# Schematic.net
KiCad netlist of a schematic drawn in Altium Designer
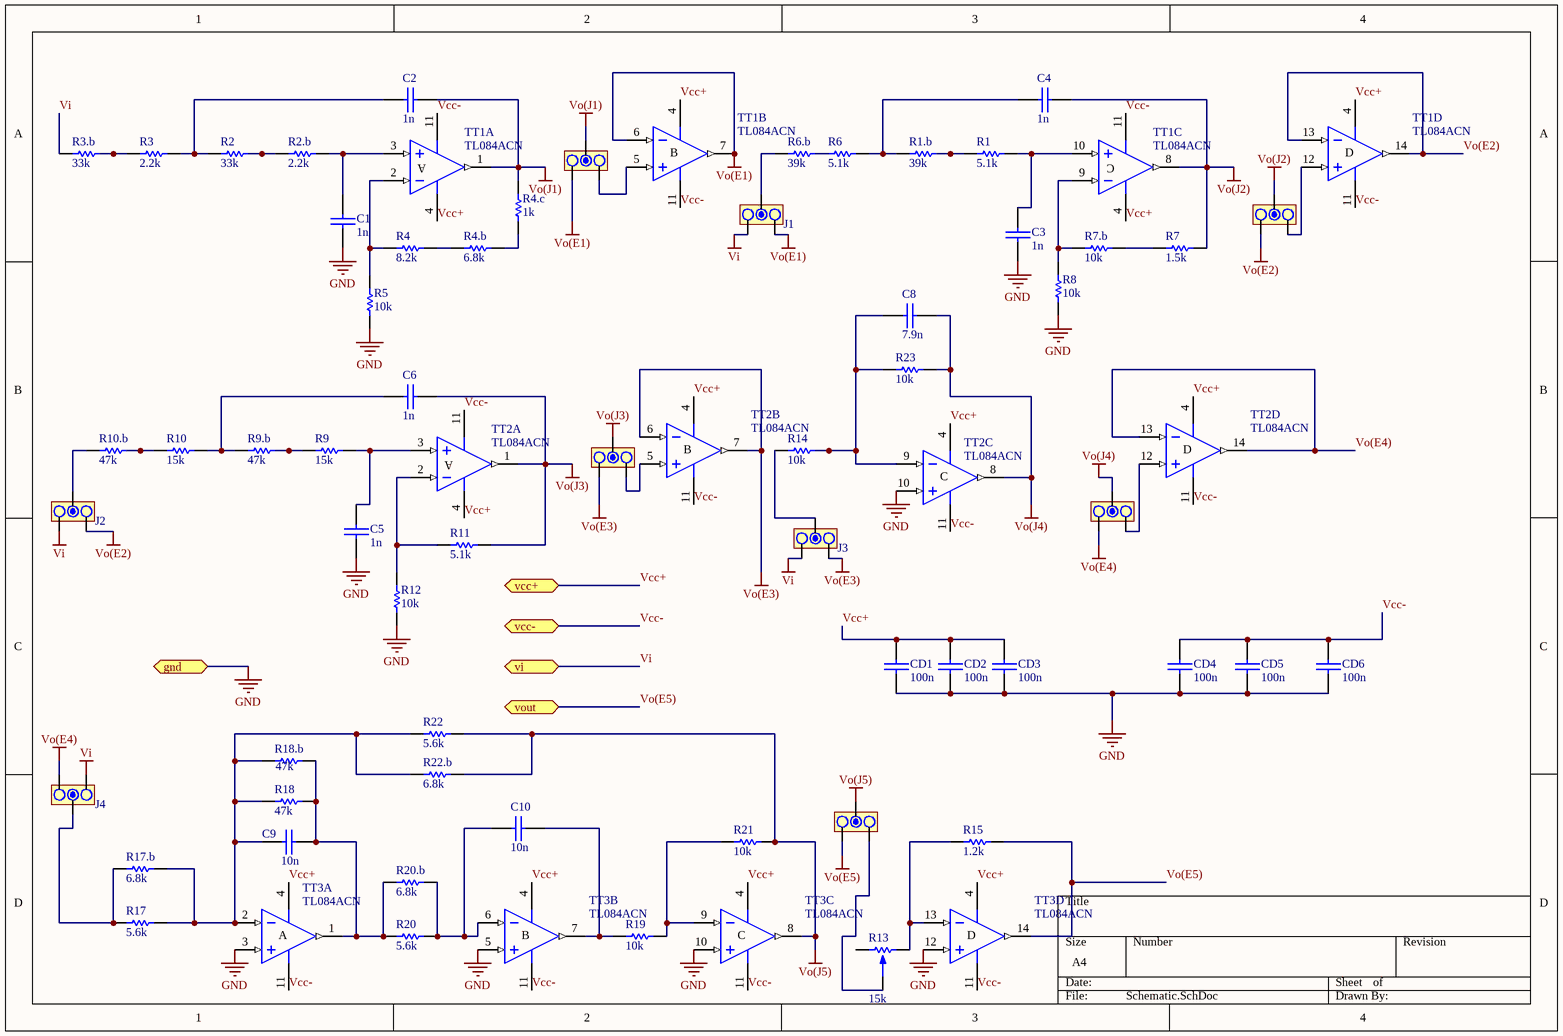
[diagram p0: Schematic.SchDoc]

(export (version "E")
  (design (tool "Eeschema 10.0.6"))
  (components
    (comp (ref "C1") (value "1n") (footprint "CAP200") (libsource (lib "LIBEBAL") (part "CAP")))
    (comp (ref "C2") (value "1n") (footprint "CAP200") (libsource (lib "LIBEBAL") (part "CAP")))
    (comp (ref "C3") (value "1n") (footprint "CAP200") (libsource (lib "LIBEBAL") (part "CAP")))
    (comp (ref "C4") (value "1n") (footprint "CAP200") (libsource (lib "LIBEBAL") (part "CAP")))
    (comp (ref "C5") (value "1n") (footprint "CAP200") (libsource (lib "LIBEBAL") (part "CAP")))
    (comp (ref "C6") (value "1n") (footprint "CAP200") (libsource (lib "LIBEBAL") (part "CAP")))
    (comp (ref "C8") (value "7.9n") (footprint "CAP200") (libsource (lib "LIBEBAL") (part "CAP")))
    (comp (ref "C9") (value "10n") (footprint "CAP200") (libsource (lib "LIBEBAL") (part "CAP")))
    (comp (ref "C10") (value "10n") (footprint "CAP200") (libsource (lib "LIBEBAL") (part "CAP")))
    (comp (ref "CD1") (value "100n") (footprint "CAP200") (libsource (lib "LIBEBAL") (part "CAP")))
    (comp (ref "CD2") (value "100n") (footprint "CAP200") (libsource (lib "LIBEBAL") (part "CAP")))
    (comp (ref "CD3") (value "100n") (footprint "CAP200") (libsource (lib "LIBEBAL") (part "CAP")))
    (comp (ref "CD4") (value "100n") (footprint "CAP200") (libsource (lib "LIBEBAL") (part "CAP")))
    (comp (ref "CD5") (value "100n") (footprint "CAP200") (libsource (lib "LIBEBAL") (part "CAP")))
    (comp (ref "CD6") (value "100n") (footprint "CAP200") (libsource (lib "LIBEBAL") (part "CAP")))
    (comp (ref "J1") (value "JUMPER") (footprint "JUMPER3") (libsource (lib "LIBEBAL") (part "JUMPER3")))
    (comp (ref "J2") (value "JUMPER") (footprint "JUMPER3") (libsource (lib "LIBEBAL") (part "JUMPER3")))
    (comp (ref "J3") (value "JUMPER") (footprint "JUMPER3") (libsource (lib "LIBEBAL") (part "JUMPER3")))
    (comp (ref "J4") (value "JUMPER") (footprint "JUMPER3") (libsource (lib "") (part "JUMPER3_1")))
    (comp (ref "Jumper1") (value "JUMPER") (footprint "JUMPER3") (libsource (lib "LIBEBAL") (part "JUMPER3")))
    (comp (ref "Jumper2") (value "JUMPER") (footprint "JUMPER3") (libsource (lib "LIBEBAL") (part "JUMPER3")))
    (comp (ref "Jumper3") (value "JUMPER") (footprint "JUMPER3") (libsource (lib "LIBEBAL") (part "JUMPER3")))
    (comp (ref "Jumper4") (value "JUMPER") (footprint "JUMPER3") (libsource (lib "LIBEBAL") (part "JUMPER3")))
    (comp (ref "Jumper5") (value "JUMPER") (footprint "JUMPER3") (libsource (lib "LIBEBAL") (part "JUMPER3")))
    (comp (ref "R1") (value "5.1k") (footprint "RES400") (libsource (lib "LIBEBAL") (part "RES")))
    (comp (ref "R1.b") (value "39k") (footprint "RES400") (libsource (lib "LIBEBAL") (part "RES")))
    (comp (ref "R2") (value "33k") (footprint "RES400") (libsource (lib "LIBEBAL") (part "RES")))
    (comp (ref "R2.b") (value "2.2k") (footprint "RES400") (libsource (lib "LIBEBAL") (part "RES")))
    (comp (ref "R3") (value "2.2k") (footprint "RES400") (libsource (lib "LIBEBAL") (part "RES")))
    (comp (ref "R3.b") (value "33k") (footprint "RES400") (libsource (lib "LIBEBAL") (part "RES")))
    (comp (ref "R4") (value "8.2k") (footprint "RES400") (libsource (lib "LIBEBAL") (part "RES")))
    (comp (ref "R4.b") (value "6.8k") (footprint "RES400") (libsource (lib "LIBEBAL") (part "RES")))
    (comp (ref "R4.c") (value "1k") (footprint "RES400") (libsource (lib "LIBEBAL") (part "RES")))
    (comp (ref "R5") (value "10k") (footprint "RES400") (libsource (lib "LIBEBAL") (part "RES")))
    (comp (ref "R6") (value "5.1k") (footprint "RES400") (libsource (lib "LIBEBAL") (part "RES")))
    (comp (ref "R6.b") (value "39k") (footprint "RES400") (libsource (lib "LIBEBAL") (part "RES")))
    (comp (ref "R7") (value "1.5k") (footprint "RES400") (libsource (lib "LIBEBAL") (part "RES")))
    (comp (ref "R7.b") (value "10k") (footprint "RES400") (libsource (lib "LIBEBAL") (part "RES")))
    (comp (ref "R8") (value "10k") (footprint "RES400") (libsource (lib "LIBEBAL") (part "RES")))
    (comp (ref "R9") (value "15k") (footprint "RES400") (libsource (lib "LIBEBAL") (part "RES")))
    (comp (ref "R9.b") (value "47k") (footprint "RES400") (libsource (lib "LIBEBAL") (part "RES")))
    (comp (ref "R10") (value "15k") (footprint "RES400") (libsource (lib "LIBEBAL") (part "RES")))
    (comp (ref "R10.b") (value "47k") (footprint "RES400") (libsource (lib "LIBEBAL") (part "RES")))
    (comp (ref "R11") (value "5.1k") (footprint "RES400") (libsource (lib "LIBEBAL") (part "RES")))
    (comp (ref "R12") (value "10k") (footprint "RES400") (libsource (lib "LIBEBAL") (part "RES")))
    (comp (ref "R13") (value "15k") (footprint "PRESET V") (libsource (lib "LIBEBAL") (part "PRESET")))
    (comp (ref "R14") (value "10k") (footprint "RES400") (libsource (lib "LIBEBAL") (part "RES")))
    (comp (ref "R15") (value "1.2k") (footprint "RES400") (libsource (lib "LIBEBAL") (part "RES")))
    (comp (ref "R17") (value "5.6k") (footprint "RES400") (libsource (lib "LIBEBAL") (part "RES")))
    (comp (ref "R17.b") (value "6.8k") (footprint "RES400") (libsource (lib "LIBEBAL") (part "RES")))
    (comp (ref "R18") (value "47k") (footprint "RES400") (libsource (lib "LIBEBAL") (part "RES")))
    (comp (ref "R18.b") (value "47k") (footprint "RES400") (libsource (lib "LIBEBAL") (part "RES")))
    (comp (ref "R19") (value "10k") (footprint "RES400") (libsource (lib "LIBEBAL") (part "RES")))
    (comp (ref "R20") (value "5.6k") (footprint "RES400") (libsource (lib "LIBEBAL") (part "RES")))
    (comp (ref "R20.b") (value "6.8k") (footprint "RES400") (libsource (lib "LIBEBAL") (part "RES")))
    (comp (ref "R21") (value "10k") (footprint "RES400") (libsource (lib "LIBEBAL") (part "RES")))
    (comp (ref "R22") (value "5.6k") (footprint "RES400") (libsource (lib "LIBEBAL") (part "RES")))
    (comp (ref "R22.b") (value "6.8k") (footprint "RES400") (libsource (lib "LIBEBAL") (part "RES")))
    (comp (ref "R23") (value "10k") (footprint "RES400") (libsource (lib "LIBEBAL") (part "RES")))
    (comp (ref "TT1")
      (value "TL084ACN")
      (footprint "DIP14")
      (description "General-Purpose J-FET Quad Operational Amplifier")
      (fields (field (name "PUBLISHER") "Altium Limited"))
      (libsource (lib "ST Operational Amplifier") (part "TL084ACN"))
    )
    (comp (ref "TT2")
      (value "TL084ACN")
      (footprint "DIP14")
      (description "General-Purpose J-FET Quad Operational Amplifier")
      (fields (field (name "PUBLISHER") "Altium Limited"))
      (libsource (lib "ST Operational Amplifier") (part "TL084ACN"))
    )
    (comp (ref "TT3")
      (value "TL084ACN")
      (footprint "DIP14")
      (description "General-Purpose J-FET Quad Operational Amplifier")
      (fields (field (name "PUBLISHER") "Altium Limited"))
      (libsource (lib "ST Operational Amplifier") (part "TL084ACN"))
    )
  )
  (nets
    (net (code "1") (name "/Vcc+") (class "Default")
      (node (ref "CD1") (pin "1") (pinfunction "1_1") (pintype "passive"))
      (node (ref "CD2") (pin "1") (pinfunction "1_1") (pintype "passive"))
      (node (ref "CD3") (pin "1") (pinfunction "1_1") (pintype "passive"))
      (node (ref "TT1") (pin "4") (pinfunction "V+_4") (pintype "power_in"))
      (node (ref "TT2") (pin "4") (pinfunction "V+_4") (pintype "power_in"))
      (node (ref "TT3") (pin "4") (pinfunction "V+_4") (pintype "power_in"))
    )
    (net (code "2") (name "/Vcc-") (class "Default")
      (node (ref "CD4") (pin "1") (pinfunction "1_1") (pintype "passive"))
      (node (ref "CD5") (pin "1") (pinfunction "1_1") (pintype "passive"))
      (node (ref "CD6") (pin "1") (pinfunction "1_1") (pintype "passive"))
      (node (ref "TT1") (pin "11") (pinfunction "V-_11") (pintype "power_in"))
      (node (ref "TT2") (pin "11") (pinfunction "V-_11") (pintype "power_in"))
      (node (ref "TT3") (pin "11") (pinfunction "V-_11") (pintype "power_in"))
    )
    (net (code "3") (name "GND") (class "Default")
      (node (ref "C1") (pin "1") (pinfunction "1_1") (pintype "passive"))
      (node (ref "C3") (pin "1") (pinfunction "1_1") (pintype "passive"))
      (node (ref "C5") (pin "1") (pinfunction "1_1") (pintype "passive"))
      (node (ref "CD1") (pin "2") (pinfunction "2_2") (pintype "passive"))
      (node (ref "CD2") (pin "2") (pinfunction "2_2") (pintype "passive"))
      (node (ref "CD3") (pin "2") (pinfunction "2_2") (pintype "passive"))
      (node (ref "CD4") (pin "2") (pinfunction "2_2") (pintype "passive"))
      (node (ref "CD5") (pin "2") (pinfunction "2_2") (pintype "passive"))
      (node (ref "CD6") (pin "2") (pinfunction "2_2") (pintype "passive"))
      (node (ref "R12") (pin "1") (pinfunction "1_1") (pintype "passive"))
      (node (ref "R5") (pin "1") (pinfunction "1_1") (pintype "passive"))
      (node (ref "R8") (pin "1") (pinfunction "1_1") (pintype "passive"))
      (node (ref "TT2") (pin "10") (pinfunction "IN+_10") (pintype "input"))
      (node (ref "TT3") (pin "10") (pinfunction "IN+_10") (pintype "input"))
      (node (ref "TT3") (pin "12") (pinfunction "IN+_12") (pintype "input"))
      (node (ref "TT3") (pin "3") (pinfunction "IN+_3") (pintype "input"))
      (node (ref "TT3") (pin "5") (pinfunction "IN+_5") (pintype "input"))
    )
    (net (code "4") (name "Net-(C2-Pad1)") (class "Default")
      (node (ref "C2") (pin "1") (pinfunction "1_1") (pintype "passive"))
      (node (ref "R2") (pin "1") (pinfunction "1_1") (pintype "passive"))
      (node (ref "R3") (pin "2") (pinfunction "2_2") (pintype "passive"))
    )
    (net (code "5") (name "Net-(C4-Pad1)") (class "Default")
      (node (ref "C4") (pin "1") (pinfunction "1_1") (pintype "passive"))
      (node (ref "R1.b") (pin "1") (pinfunction "1_1") (pintype "passive"))
      (node (ref "R6") (pin "2") (pinfunction "2_2") (pintype "passive"))
    )
    (net (code "6") (name "Net-(C6-Pad1)") (class "Default")
      (node (ref "C6") (pin "1") (pinfunction "1_1") (pintype "passive"))
      (node (ref "R10") (pin "2") (pinfunction "2_2") (pintype "passive"))
      (node (ref "R9.b") (pin "1") (pinfunction "1_1") (pintype "passive"))
    )
    (net (code "7") (name "Net-(J1-Pad2)") (class "Default")
      (node (ref "J1") (pin "2") (pinfunction "2_2") (pintype "passive"))
      (node (ref "R6.b") (pin "1") (pinfunction "1_1") (pintype "passive"))
    )
    (net (code "8") (name "Net-(J2-Pad2)") (class "Default")
      (node (ref "J2") (pin "2") (pinfunction "2_2") (pintype "passive"))
      (node (ref "R10.b") (pin "1") (pinfunction "1_1") (pintype "passive"))
    )
    (net (code "9") (name "Net-(J3-Pad2)") (class "Default")
      (node (ref "J3") (pin "2") (pinfunction "2_2") (pintype "passive"))
      (node (ref "R14") (pin "1") (pinfunction "1_1") (pintype "passive"))
    )
    (net (code "10") (name "Net-(J4-Pad2)") (class "Default")
      (node (ref "J4") (pin "2") (pinfunction "2_2") (pintype "passive"))
      (node (ref "R17") (pin "1") (pinfunction "1_1") (pintype "passive"))
      (node (ref "R17.b") (pin "1") (pinfunction "1_1") (pintype "passive"))
    )
    (net (code "11") (name "Net-(Jumper5-Pad1)") (class "Default")
      (node (ref "Jumper5") (pin "1") (pinfunction "1_1") (pintype "passive"))
      (node (ref "R13") (pin "2") (pinfunction "2_2") (pintype "passive"))
    )
    (net (code "12") (name "Net-(R1-Pad1)") (class "Default")
      (node (ref "R1") (pin "1") (pinfunction "1_1") (pintype "passive"))
      (node (ref "R1.b") (pin "2") (pinfunction "2_2") (pintype "passive"))
    )
    (net (code "13") (name "Net-(R2-Pad2)") (class "Default")
      (node (ref "R2") (pin "2") (pinfunction "2_2") (pintype "passive"))
      (node (ref "R2.b") (pin "1") (pinfunction "1_1") (pintype "passive"))
    )
    (net (code "14") (name "Net-(R3-Pad1)") (class "Default")
      (node (ref "R3") (pin "1") (pinfunction "1_1") (pintype "passive"))
      (node (ref "R3.b") (pin "2") (pinfunction "2_2") (pintype "passive"))
    )
    (net (code "15") (name "Net-(R4-Pad1)") (class "Default")
      (node (ref "R4") (pin "1") (pinfunction "1_1") (pintype "passive"))
      (node (ref "R4.b") (pin "1") (pinfunction "1_1") (pintype "passive"))
    )
    (net (code "16") (name "Net-(R4.b-Pad2)") (class "Default")
      (node (ref "R4.b") (pin "2") (pinfunction "2_2") (pintype "passive"))
      (node (ref "R4.c") (pin "1") (pinfunction "1_1") (pintype "passive"))
    )
    (net (code "17") (name "Net-(R6-Pad1)") (class "Default")
      (node (ref "R6") (pin "1") (pinfunction "1_1") (pintype "passive"))
      (node (ref "R6.b") (pin "2") (pinfunction "2_2") (pintype "passive"))
    )
    (net (code "18") (name "Net-(R7-Pad1)") (class "Default")
      (node (ref "R7") (pin "1") (pinfunction "1_1") (pintype "passive"))
      (node (ref "R7.b") (pin "1") (pinfunction "1_1") (pintype "passive"))
    )
    (net (code "19") (name "Net-(R9-Pad1)") (class "Default")
      (node (ref "R9") (pin "1") (pinfunction "1_1") (pintype "passive"))
      (node (ref "R9.b") (pin "2") (pinfunction "2_2") (pintype "passive"))
    )
    (net (code "20") (name "Net-(R10-Pad1)") (class "Default")
      (node (ref "R10") (pin "1") (pinfunction "1_1") (pintype "passive"))
      (node (ref "R10.b") (pin "2") (pinfunction "2_2") (pintype "passive"))
    )
    (net (code "21") (name "Net-(TT1A-IN+)") (class "Default")
      (node (ref "C1") (pin "2") (pinfunction "2_2") (pintype "passive"))
      (node (ref "R2.b") (pin "2") (pinfunction "2_2") (pintype "passive"))
      (node (ref "TT1") (pin "3") (pinfunction "IN+_3") (pintype "input"))
    )
    (net (code "22") (name "Net-(TT1A-IN-)") (class "Default")
      (node (ref "R4") (pin "2") (pinfunction "2_2") (pintype "passive"))
      (node (ref "R5") (pin "2") (pinfunction "2_2") (pintype "passive"))
      (node (ref "TT1") (pin "2") (pinfunction "IN-_2") (pintype "input"))
    )
    (net (code "23") (name "Net-(TT1B-IN+)") (class "Default")
      (node (ref "Jumper1") (pin "1") (pinfunction "1_1") (pintype "passive"))
      (node (ref "TT1") (pin "5") (pinfunction "IN+_5") (pintype "input"))
    )
    (net (code "24") (name "Net-(TT1C-IN+)") (class "Default")
      (node (ref "C3") (pin "2") (pinfunction "2_2") (pintype "passive"))
      (node (ref "R1") (pin "2") (pinfunction "2_2") (pintype "passive"))
      (node (ref "TT1") (pin "10") (pinfunction "IN+_10") (pintype "input"))
    )
    (net (code "25") (name "Net-(TT1C-IN-)") (class "Default")
      (node (ref "R7.b") (pin "2") (pinfunction "2_2") (pintype "passive"))
      (node (ref "R8") (pin "2") (pinfunction "2_2") (pintype "passive"))
      (node (ref "TT1") (pin "9") (pinfunction "IN-_9") (pintype "input"))
    )
    (net (code "26") (name "Net-(TT1D-IN+)") (class "Default")
      (node (ref "Jumper2") (pin "1") (pinfunction "1_1") (pintype "passive"))
      (node (ref "TT1") (pin "12") (pinfunction "IN+_12") (pintype "input"))
    )
    (net (code "27") (name "Net-(TT2A-IN+)") (class "Default")
      (node (ref "C5") (pin "2") (pinfunction "2_2") (pintype "passive"))
      (node (ref "R9") (pin "2") (pinfunction "2_2") (pintype "passive"))
      (node (ref "TT2") (pin "3") (pinfunction "IN+_3") (pintype "input"))
    )
    (net (code "28") (name "Net-(TT2A-IN-)") (class "Default")
      (node (ref "R11") (pin "2") (pinfunction "2_2") (pintype "passive"))
      (node (ref "R12") (pin "2") (pinfunction "2_2") (pintype "passive"))
      (node (ref "TT2") (pin "2") (pinfunction "IN-_2") (pintype "input"))
    )
    (net (code "29") (name "Net-(TT2B-IN+)") (class "Default")
      (node (ref "Jumper3") (pin "1") (pinfunction "1_1") (pintype "passive"))
      (node (ref "TT2") (pin "5") (pinfunction "IN+_5") (pintype "input"))
    )
    (net (code "30") (name "Net-(TT2C-IN-)") (class "Default")
      (node (ref "C8") (pin "1") (pinfunction "1_1") (pintype "passive"))
      (node (ref "R14") (pin "2") (pinfunction "2_2") (pintype "passive"))
      (node (ref "R23") (pin "1") (pinfunction "1_1") (pintype "passive"))
      (node (ref "TT2") (pin "9") (pinfunction "IN-_9") (pintype "input"))
    )
    (net (code "31") (name "Net-(TT2D-IN+)") (class "Default")
      (node (ref "Jumper4") (pin "1") (pinfunction "1_1") (pintype "passive"))
      (node (ref "TT2") (pin "12") (pinfunction "IN+_12") (pintype "input"))
    )
    (net (code "32") (name "Net-(TT3A-IN-)") (class "Default")
      (node (ref "C9") (pin "1") (pinfunction "1_1") (pintype "passive"))
      (node (ref "R17") (pin "2") (pinfunction "2_2") (pintype "passive"))
      (node (ref "R17.b") (pin "2") (pinfunction "2_2") (pintype "passive"))
      (node (ref "R18") (pin "1") (pinfunction "1_1") (pintype "passive"))
      (node (ref "R18.b") (pin "1") (pinfunction "1_1") (pintype "passive"))
      (node (ref "R22") (pin "1") (pinfunction "1_1") (pintype "passive"))
      (node (ref "R22.b") (pin "1") (pinfunction "1_1") (pintype "passive"))
      (node (ref "TT3") (pin "2") (pinfunction "IN-_2") (pintype "input"))
    )
    (net (code "33") (name "Net-(TT3A-OUT)") (class "Default")
      (node (ref "C9") (pin "2") (pinfunction "2_2") (pintype "passive"))
      (node (ref "R18") (pin "2") (pinfunction "2_2") (pintype "passive"))
      (node (ref "R18.b") (pin "2") (pinfunction "2_2") (pintype "passive"))
      (node (ref "R20") (pin "1") (pinfunction "1_1") (pintype "passive"))
      (node (ref "R20.b") (pin "1") (pinfunction "1_1") (pintype "passive"))
      (node (ref "TT3") (pin "1") (pinfunction "OUT_1") (pintype "output"))
    )
    (net (code "34") (name "Net-(TT3B-IN-)") (class "Default")
      (node (ref "C10") (pin "1") (pinfunction "1_1") (pintype "passive"))
      (node (ref "R20") (pin "2") (pinfunction "2_2") (pintype "passive"))
      (node (ref "R20.b") (pin "2") (pinfunction "2_2") (pintype "passive"))
      (node (ref "TT3") (pin "6") (pinfunction "IN-_6") (pintype "input"))
    )
    (net (code "35") (name "Net-(TT3B-OUT)") (class "Default")
      (node (ref "C10") (pin "2") (pinfunction "2_2") (pintype "passive"))
      (node (ref "R19") (pin "1") (pinfunction "1_1") (pintype "passive"))
      (node (ref "TT3") (pin "7") (pinfunction "OUT_7") (pintype "output"))
    )
    (net (code "36") (name "Net-(TT3C-IN-)") (class "Default")
      (node (ref "R19") (pin "2") (pinfunction "2_2") (pintype "passive"))
      (node (ref "R21") (pin "1") (pinfunction "1_1") (pintype "passive"))
      (node (ref "TT3") (pin "9") (pinfunction "IN-_9") (pintype "input"))
    )
    (net (code "37") (name "Net-(TT3D-IN-)") (class "Default")
      (node (ref "R13") (pin "1") (pinfunction "1_1") (pintype "passive"))
      (node (ref "R15") (pin "1") (pinfunction "1_1") (pintype "passive"))
      (node (ref "TT3") (pin "13") (pinfunction "IN-_13") (pintype "input"))
    )
    (net (code "38") (name "Vi") (class "Default")
      (node (ref "J1") (pin "3") (pinfunction "3_3") (pintype "passive"))
      (node (ref "J2") (pin "3") (pinfunction "3_3") (pintype "passive"))
      (node (ref "J3") (pin "3") (pinfunction "3_3") (pintype "passive"))
      (node (ref "J4") (pin "3") (pinfunction "3_3") (pintype "passive"))
      (node (ref "R3.b") (pin "1") (pinfunction "1_1") (pintype "passive"))
    )
    (net (code "39") (name "Vo(E1)") (class "Default")
      (node (ref "J1") (pin "1") (pinfunction "1_1") (pintype "passive"))
      (node (ref "Jumper1") (pin "3") (pinfunction "3_3") (pintype "passive"))
      (node (ref "TT1") (pin "6") (pinfunction "IN-_6") (pintype "input"))
      (node (ref "TT1") (pin "7") (pinfunction "OUT_7") (pintype "output"))
    )
    (net (code "40") (name "Vo(E2)") (class "Default")
      (node (ref "J2") (pin "1") (pinfunction "1_1") (pintype "passive"))
      (node (ref "Jumper2") (pin "3") (pinfunction "3_3") (pintype "passive"))
      (node (ref "TT1") (pin "13") (pinfunction "IN-_13") (pintype "input"))
      (node (ref "TT1") (pin "14") (pinfunction "OUT_14") (pintype "output"))
    )
    (net (code "41") (name "Vo(E3)") (class "Default")
      (node (ref "J3") (pin "1") (pinfunction "1_1") (pintype "passive"))
      (node (ref "Jumper3") (pin "3") (pinfunction "3_3") (pintype "passive"))
      (node (ref "TT2") (pin "6") (pinfunction "IN-_6") (pintype "input"))
      (node (ref "TT2") (pin "7") (pinfunction "OUT_7") (pintype "output"))
    )
    (net (code "42") (name "Vo(E4)") (class "Default")
      (node (ref "J4") (pin "1") (pinfunction "1_1") (pintype "passive"))
      (node (ref "Jumper4") (pin "3") (pinfunction "3_3") (pintype "passive"))
      (node (ref "TT2") (pin "13") (pinfunction "IN-_13") (pintype "input"))
      (node (ref "TT2") (pin "14") (pinfunction "OUT_14") (pintype "output"))
    )
    (net (code "43") (name "Vo(E5)") (class "Default")
      (node (ref "Jumper5") (pin "3") (pinfunction "3_3") (pintype "passive"))
      (node (ref "R15") (pin "2") (pinfunction "2_2") (pintype "passive"))
      (node (ref "TT3") (pin "14") (pinfunction "OUT_14") (pintype "output"))
    )
    (net (code "44") (name "Vo(J1)") (class "Default")
      (node (ref "C2") (pin "2") (pinfunction "2_2") (pintype "passive"))
      (node (ref "Jumper1") (pin "2") (pinfunction "2_2") (pintype "passive"))
      (node (ref "R4.c") (pin "2") (pinfunction "2_2") (pintype "passive"))
      (node (ref "TT1") (pin "1") (pinfunction "OUT_1") (pintype "output"))
    )
    (net (code "45") (name "Vo(J2)") (class "Default")
      (node (ref "C4") (pin "2") (pinfunction "2_2") (pintype "passive"))
      (node (ref "Jumper2") (pin "2") (pinfunction "2_2") (pintype "passive"))
      (node (ref "R7") (pin "2") (pinfunction "2_2") (pintype "passive"))
      (node (ref "TT1") (pin "8") (pinfunction "OUT_8") (pintype "output"))
    )
    (net (code "46") (name "Vo(J3)") (class "Default")
      (node (ref "C6") (pin "2") (pinfunction "2_2") (pintype "passive"))
      (node (ref "Jumper3") (pin "2") (pinfunction "2_2") (pintype "passive"))
      (node (ref "R11") (pin "1") (pinfunction "1_1") (pintype "passive"))
      (node (ref "TT2") (pin "1") (pinfunction "OUT_1") (pintype "output"))
    )
    (net (code "47") (name "Vo(J4)") (class "Default")
      (node (ref "C8") (pin "2") (pinfunction "2_2") (pintype "passive"))
      (node (ref "Jumper4") (pin "2") (pinfunction "2_2") (pintype "passive"))
      (node (ref "R23") (pin "2") (pinfunction "2_2") (pintype "passive"))
      (node (ref "TT2") (pin "8") (pinfunction "OUT_8") (pintype "output"))
    )
    (net (code "48") (name "Vo(J5)") (class "Default")
      (node (ref "Jumper5") (pin "2") (pinfunction "2_2") (pintype "passive"))
      (node (ref "R21") (pin "2") (pinfunction "2_2") (pintype "passive"))
      (node (ref "R22") (pin "2") (pinfunction "2_2") (pintype "passive"))
      (node (ref "R22.b") (pin "2") (pinfunction "2_2") (pintype "passive"))
      (node (ref "TT3") (pin "8") (pinfunction "OUT_8") (pintype "output"))
    )
    (net (code "49") (name "unconnected-(R13-Pad3)") (class "Default")
      (node (ref "R13") (pin "3") (pinfunction "3_3") (pintype "passive"))
    )
  )
)
